# circuito_domotica_damiano.net
KiCad netlist of a schematic drawn in EAGLE
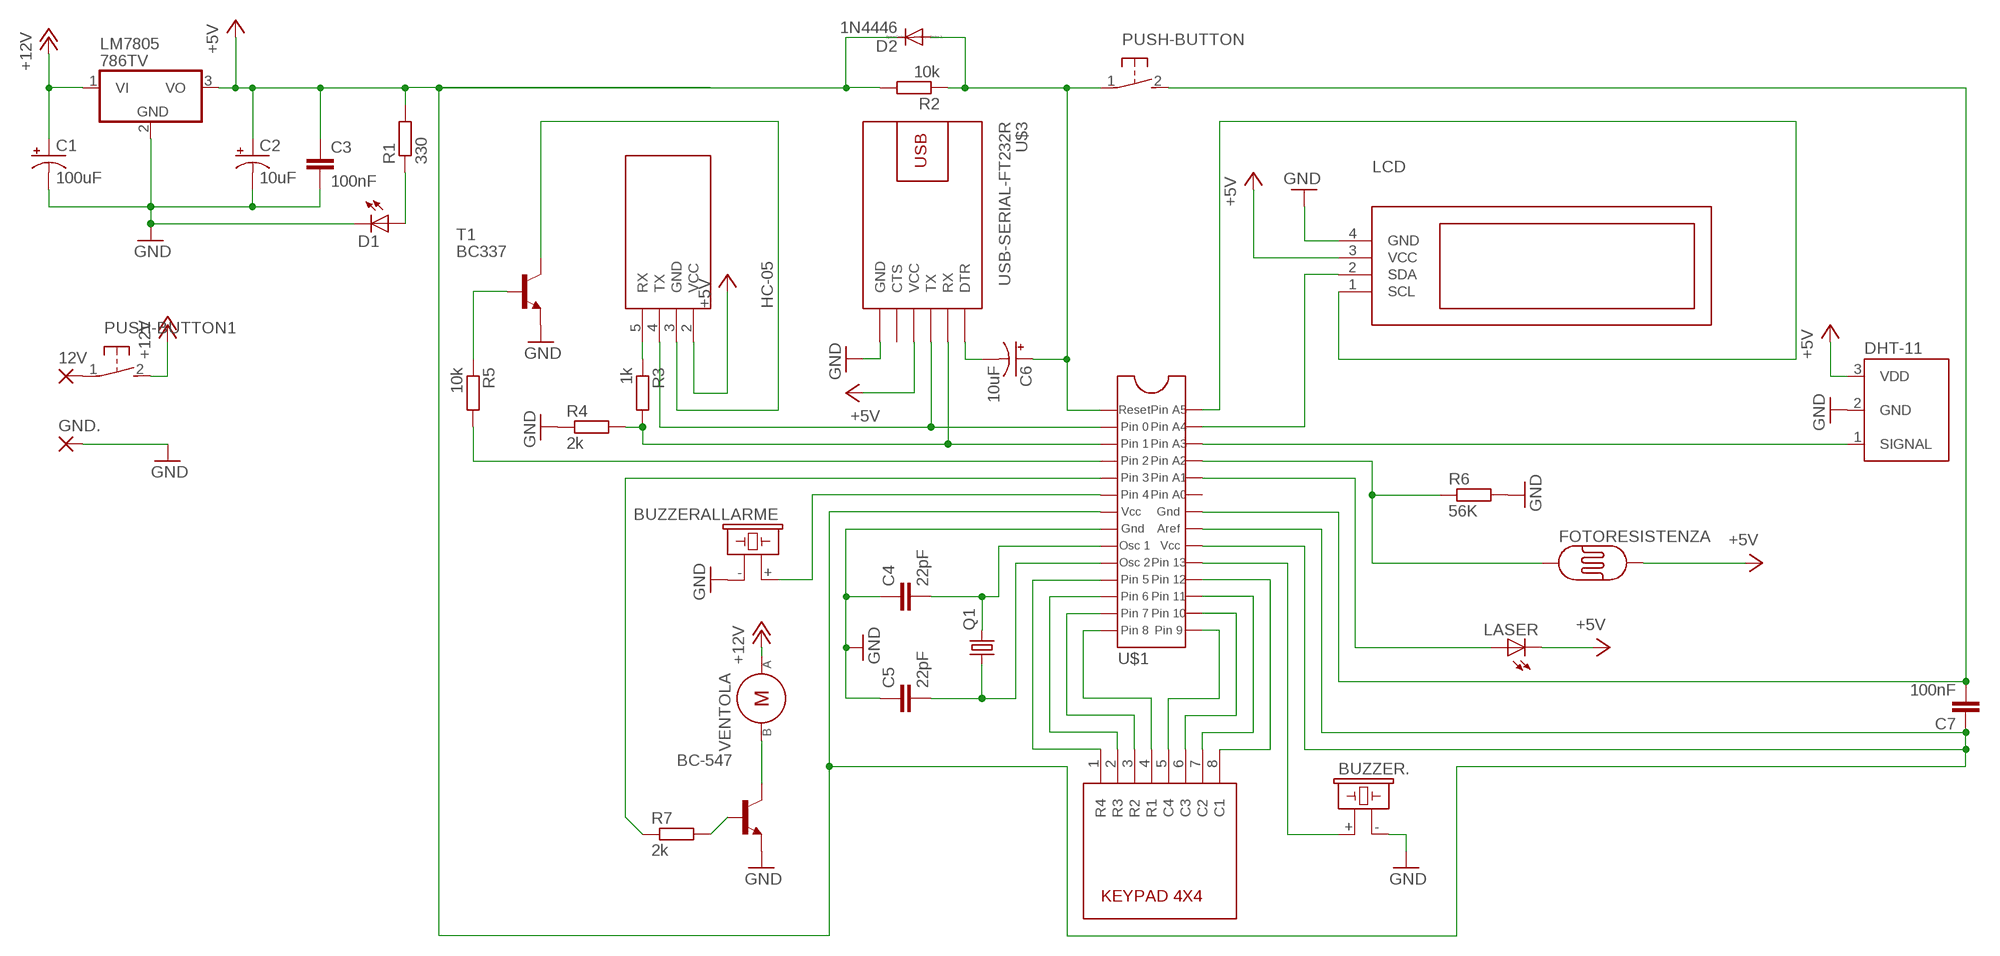
[diagram p0: schematic, sheet 1]

(export (version "E")
  (design (tool "Eeschema 10.0.6"))
  (components
    (comp (ref "12V")
      (value "WIREPAD1,6/0,8")
      (footprint "eagle-import:1,6_0,8")
      (libsource (lib "eagle-import") (part "WIREPAD1,6/0,8"))
    )
    (comp (ref "BC-547")
      (value "BC547-NPN-TO92-CBE")
      (footprint "eagle-import:TO92-CBE")
      (libsource (lib "eagle-import") (part "-NPN-TO92-CBEBC547"))
    )
    (comp (ref "BUZZER.")
      (value "BPT-24X")
      (footprint "eagle-import:BPT-24X")
      (libsource (lib "eagle-import") (part "BPT-24X"))
    )
    (comp (ref "BUZZERALLARME")
      (value "BPT-24X")
      (footprint "eagle-import:BPT-24X")
      (libsource (lib "eagle-import") (part "BPT-24X"))
    )
    (comp (ref "C1")
      (value "100uF")
      (footprint "eagle-import:E2,5-6E")
      (libsource (lib "eagle-import") (part "CPOL-USE2,5-6E"))
    )
    (comp (ref "C2")
      (value "10uF")
      (footprint "eagle-import:E2,5-6E")
      (libsource (lib "eagle-import") (part "CPOL-USE2,5-6E"))
    )
    (comp (ref "C3")
      (value "100nF")
      (footprint "eagle-import:C025-030X050")
      (libsource (lib "eagle-import") (part "C-EU025-030X050"))
    )
    (comp (ref "C4")
      (value "22pF")
      (footprint "eagle-import:C025-030X050")
      (libsource (lib "eagle-import") (part "C-EU025-030X050"))
    )
    (comp (ref "C5")
      (value "22pF")
      (footprint "eagle-import:C025-030X050")
      (libsource (lib "eagle-import") (part "C-EU025-030X050"))
    )
    (comp (ref "C6")
      (value "10uF")
      (footprint "eagle-import:E2,5-6E")
      (libsource (lib "eagle-import") (part "CPOL-USE2,5-6E"))
    )
    (comp (ref "C7")
      (value "100nF")
      (footprint "eagle-import:C025-030X050")
      (libsource (lib "eagle-import") (part "C-EU025-030X050"))
    )
    (comp (ref "D1")
      (value "SFH482")
      (footprint "eagle-import:SFH482")
      (libsource (lib "eagle-import") (part "SFH482"))
    )
    (comp (ref "D2")
      (value "1N4446")
      (footprint "eagle-import:DO35-10")
      (libsource (lib "eagle-import") (part "1N4446"))
    )
    (comp (ref "DHT-11")
      (value "DS18B20")
      (footprint "eagle-import:TO-92-AMMO")
      (libsource (lib "eagle-import") (part "DS18B20"))
    )
    (comp (ref "FOTORESISTENZA")
      (value "PHOTOCELLPTH")
      (footprint "eagle-import:PHOTOCELL")
      (libsource (lib "eagle-import") (part "PHOTOCELLPTH"))
    )
    (comp (ref "GND.")
      (value "WIREPAD1,6/0,8")
      (footprint "eagle-import:1,6_0,8")
      (libsource (lib "eagle-import") (part "WIREPAD1,6/0,8"))
    )
    (comp (ref "HC-05")
      (value "WIRELESS-BLUETOOTH-HC-05")
      (footprint "eagle-import:WIRELESS-BLUETOOTH-HC-05")
      (libsource (lib "eagle-import") (part "WIRELESS-BLUETOOTH-HC-05"))
    )
    (comp (ref "LASER")
      (value "SFH482")
      (footprint "eagle-import:SFH482")
      (libsource (lib "eagle-import") (part "SFH482"))
    )
    (comp (ref "LCD")
      (value "DISPLAY-OLED-128X32")
      (footprint "eagle-import:DISPLAY-OLED-128X32")
      (libsource (lib "eagle-import") (part "DISPLAY-OLED-128X32"))
    )
    (comp (ref "LM7805")
      (value "786TV")
      (footprint "eagle-import:TO220V")
      (libsource (lib "eagle-import") (part "78TV6"))
    )
    (comp (ref "PUSH-BUTTON")
      (value "DTS-3")
      (footprint "eagle-import:DTS-3")
      (libsource (lib "eagle-import") (part "DTS-3"))
    )
    (comp (ref "PUSH-BUTTON1")
      (value "DTS-3")
      (footprint "eagle-import:DTS-3")
      (libsource (lib "eagle-import") (part "DTS-3"))
    )
    (comp (ref "Q1")
      (value "CRYSTALHC49S")
      (footprint "eagle-import:HC49_S")
      (libsource (lib "eagle-import") (part "CRYSTALHC49S"))
    )
    (comp (ref "R1")
      (value "330")
      (footprint "eagle-import:0207_10")
      (libsource (lib "eagle-import") (part "R-EU_0207/10"))
    )
    (comp (ref "R2")
      (value "10k")
      (footprint "eagle-import:0207_10")
      (libsource (lib "eagle-import") (part "R-EU_0207/10"))
    )
    (comp (ref "R3")
      (value "1k")
      (footprint "eagle-import:0207_10")
      (libsource (lib "eagle-import") (part "R-EU_0207/10"))
    )
    (comp (ref "R4")
      (value "2k")
      (footprint "eagle-import:0207_10")
      (libsource (lib "eagle-import") (part "R-EU_0207/10"))
    )
    (comp (ref "R5")
      (value "10k")
      (footprint "eagle-import:0207_10")
      (libsource (lib "eagle-import") (part "R-EU_0207/10"))
    )
    (comp (ref "R6")
      (value "56K")
      (footprint "eagle-import:0207_10")
      (libsource (lib "eagle-import") (part "R-EU_0207/10"))
    )
    (comp (ref "R7")
      (value "2k")
      (footprint "eagle-import:0207_10")
      (libsource (lib "eagle-import") (part "R-EU_0207/10"))
    )
    (comp (ref "T1")
      (value "BC337")
      (footprint "eagle-import:TO92")
      (libsource (lib "eagle-import") (part "BC337"))
    )
    (comp (ref "U$1")
      (value "DEVU")
      (footprint "eagle-import:PACU")
      (libsource (lib "eagle-import") (part "DEVU"))
    )
    (comp (ref "U$2")
      (value "KEYPAD4X4")
      (footprint "eagle-import:KEYPAD4X4")
      (libsource (lib "eagle-import") (part "KEYPAD4X4"))
    )
    (comp (ref "U$3")
      (value "USB-SERIAL-FT232R")
      (footprint "eagle-import:USB-SERIAL-FT232R")
      (libsource (lib "eagle-import") (part "USB-SERIAL-FT232R"))
    )
    (comp (ref "VENTOLA")
      (value "DEVU4")
      (footprint "eagle-import:PACU4")
      (libsource (lib "eagle-import") (part "DEVU4"))
    )
  )
  (nets
    (net (code "1") (name "+5V") (class "Default")
      (node (ref "C2") (pin "+") (pinfunction "+_+") (pintype "passive"))
      (node (ref "C3") (pin "1") (pinfunction "1_1") (pintype "passive"))
      (node (ref "C7") (pin "1") (pinfunction "1_1") (pintype "passive"))
      (node (ref "D2") (pin "C") (pinfunction "C_C") (pintype "passive"))
      (node (ref "DHT-11") (pin "3") (pinfunction "VDD_3") (pintype "power_in"))
      (node (ref "FOTORESISTENZA") (pin "2") (pinfunction "P$2_2") (pintype "bidirectional"))
      (node (ref "HC-05") (pin "2") (pinfunction "VCC_2") (pintype "bidirectional"))
      (node (ref "LASER") (pin "K") (pinfunction "C_K") (pintype "passive"))
      (node (ref "LCD") (pin "3") (pinfunction "VCC_3") (pintype "bidirectional"))
      (node (ref "LM7805") (pin "3") (pinfunction "VO_3") (pintype "passive"))
      (node (ref "R1") (pin "2") (pinfunction "2_2") (pintype "passive"))
      (node (ref "R2") (pin "2") (pinfunction "2_2") (pintype "passive"))
      (node (ref "U$1") (pin "20") (pinfunction "VCC1_20") (pintype "bidirectional"))
      (node (ref "U$1") (pin "21") (pinfunction "AREF_21") (pintype "bidirectional"))
      (node (ref "U$1") (pin "7") (pinfunction "VCC_7") (pintype "bidirectional"))
      (node (ref "U$3") (pin "4") (pinfunction "VCC_4") (pintype "power_in"))
    )
    (net (code "2") (name "+12V") (class "Default")
      (node (ref "C1") (pin "+") (pinfunction "+_+") (pintype "passive"))
      (node (ref "LM7805") (pin "1") (pinfunction "VI_1") (pintype "input"))
      (node (ref "PUSH-BUTTON1") (pin "2") (pinfunction "2_2") (pintype "passive"))
      (node (ref "VENTOLA") (pin "P$1") (pinfunction "P$1_P$1") (pintype "bidirectional"))
    )
    (net (code "3") (name "GND") (class "Default")
      (node (ref "BC-547") (pin "E") (pinfunction "E_E") (pintype "passive"))
      (node (ref "BUZZER.") (pin "-") (pinfunction "2_-") (pintype "passive"))
      (node (ref "BUZZERALLARME") (pin "-") (pinfunction "2_-") (pintype "passive"))
      (node (ref "C1") (pin "-") (pinfunction "-_-") (pintype "passive"))
      (node (ref "C2") (pin "-") (pinfunction "-_-") (pintype "passive"))
      (node (ref "C3") (pin "2") (pinfunction "2_2") (pintype "passive"))
      (node (ref "C4") (pin "1") (pinfunction "1_1") (pintype "passive"))
      (node (ref "C5") (pin "1") (pinfunction "1_1") (pintype "passive"))
      (node (ref "D1") (pin "K") (pinfunction "C_K") (pintype "passive"))
      (node (ref "DHT-11") (pin "2") (pinfunction "GND_2") (pintype "bidirectional"))
      (node (ref "GND.") (pin "1") (pinfunction "P_1") (pintype "passive"))
      (node (ref "LCD") (pin "4") (pinfunction "GND_4") (pintype "bidirectional"))
      (node (ref "LM7805") (pin "2") (pinfunction "GND_2") (pintype "passive"))
      (node (ref "R4") (pin "1") (pinfunction "1_1") (pintype "passive"))
      (node (ref "R6") (pin "2") (pinfunction "2_2") (pintype "passive"))
      (node (ref "T1") (pin "1") (pinfunction "E_1") (pintype "passive"))
      (node (ref "U$1") (pin "8") (pinfunction "GND_8") (pintype "bidirectional"))
      (node (ref "U$3") (pin "6") (pinfunction "GND_6") (pintype "bidirectional"))
    )
    (net (code "4") (name "Net-(12V-P)") (class "Default")
      (node (ref "12V") (pin "1") (pinfunction "P_1") (pintype "passive"))
      (node (ref "PUSH-BUTTON1") (pin "1") (pinfunction "1_1") (pintype "passive"))
    )
    (net (code "5") (name "Net-(BC-547-PadB)") (class "Default")
      (node (ref "BC-547") (pin "B") (pinfunction "B_B") (pintype "passive"))
      (node (ref "R7") (pin "2") (pinfunction "2_2") (pintype "passive"))
    )
    (net (code "6") (name "Net-(BC-547-PadC)") (class "Default")
      (node (ref "BC-547") (pin "C") (pinfunction "C_C") (pintype "passive"))
      (node (ref "VENTOLA") (pin "P$2") (pinfunction "P$2_P$2") (pintype "bidirectional"))
    )
    (net (code "7") (name "Net-(BUZZER.-1)") (class "Default")
      (node (ref "BUZZER.") (pin "+") (pinfunction "1_+") (pintype "passive"))
      (node (ref "U$1") (pin "19") (pinfunction "PIN13_19") (pintype "bidirectional"))
    )
    (net (code "8") (name "Net-(BUZZERALLARME-1)") (class "Default")
      (node (ref "BUZZERALLARME") (pin "+") (pinfunction "1_+") (pintype "passive"))
      (node (ref "U$1") (pin "6") (pinfunction "PIN4_6") (pintype "bidirectional"))
    )
    (net (code "9") (name "Net-(D1-PadA)") (class "Default")
      (node (ref "D1") (pin "A") (pinfunction "A_A") (pintype "passive"))
      (node (ref "R1") (pin "1") (pinfunction "1_1") (pintype "passive"))
    )
    (net (code "10") (name "Net-(DHT-11-SIGNAL)") (class "Default")
      (node (ref "DHT-11") (pin "1") (pinfunction "SIGNAL_1") (pintype "power_in"))
      (node (ref "U$1") (pin "26") (pinfunction "PINA3_26") (pintype "bidirectional"))
    )
    (net (code "11") (name "Net-(FOTORESISTENZA-P$1)") (class "Default")
      (node (ref "FOTORESISTENZA") (pin "1") (pinfunction "P$1_1") (pintype "bidirectional"))
      (node (ref "R6") (pin "1") (pinfunction "1_1") (pintype "passive"))
      (node (ref "U$1") (pin "25") (pinfunction "PINA2_25") (pintype "bidirectional"))
    )
    (net (code "12") (name "Net-(HC-05-GND)") (class "Default")
      (node (ref "HC-05") (pin "3") (pinfunction "GND_3") (pintype "bidirectional"))
      (node (ref "T1") (pin "3") (pinfunction "C_3") (pintype "passive"))
    )
    (net (code "13") (name "Net-(HC-05-RX)") (class "Default")
      (node (ref "HC-05") (pin "5") (pinfunction "RX_5") (pintype "power_in"))
      (node (ref "R3") (pin "1") (pinfunction "1_1") (pintype "passive"))
    )
    (net (code "14") (name "Net-(HC-05-TX)") (class "Default")
      (node (ref "HC-05") (pin "4") (pinfunction "TX_4") (pintype "power_in"))
      (node (ref "U$1") (pin "2") (pinfunction "PIN0_2") (pintype "bidirectional"))
      (node (ref "U$3") (pin "3") (pinfunction "TX_3") (pintype "bidirectional"))
    )
    (net (code "15") (name "Net-(LCD-SCL)") (class "Default")
      (node (ref "LCD") (pin "1") (pinfunction "SCL_1") (pintype "power_in"))
      (node (ref "U$1") (pin "28") (pinfunction "PINA5_28") (pintype "bidirectional"))
    )
    (net (code "16") (name "Net-(LCD-SDA)") (class "Default")
      (node (ref "LCD") (pin "2") (pinfunction "SDA_2") (pintype "power_in"))
      (node (ref "U$1") (pin "27") (pinfunction "PINA4_27") (pintype "bidirectional"))
    )
    (net (code "17") (name "Net-(T1-B)") (class "Default")
      (node (ref "R5") (pin "1") (pinfunction "1_1") (pintype "passive"))
      (node (ref "T1") (pin "2") (pinfunction "B_2") (pintype "passive"))
    )
    (net (code "18") (name "Net-(U$1-GND1)") (class "Default")
      (node (ref "C7") (pin "2") (pinfunction "2_2") (pintype "passive"))
      (node (ref "PUSH-BUTTON") (pin "2") (pinfunction "2_2") (pintype "passive"))
      (node (ref "U$1") (pin "22") (pinfunction "GND1_22") (pintype "bidirectional"))
    )
    (net (code "19") (name "Net-(U$1-PIN1)") (class "Default")
      (node (ref "R3") (pin "2") (pinfunction "2_2") (pintype "passive"))
      (node (ref "R4") (pin "2") (pinfunction "2_2") (pintype "passive"))
      (node (ref "U$1") (pin "3") (pinfunction "PIN1_3") (pintype "bidirectional"))
      (node (ref "U$3") (pin "2") (pinfunction "RX_2") (pintype "bidirectional"))
    )
    (net (code "20") (name "Net-(U$1-PIN2)") (class "Default")
      (node (ref "R5") (pin "2") (pinfunction "2_2") (pintype "passive"))
      (node (ref "U$1") (pin "4") (pinfunction "PIN2_4") (pintype "bidirectional"))
    )
    (net (code "21") (name "Net-(U$1-PIN3)") (class "Default")
      (node (ref "R7") (pin "1") (pinfunction "1_1") (pintype "passive"))
      (node (ref "U$1") (pin "5") (pinfunction "PIN3_5") (pintype "bidirectional"))
    )
    (net (code "22") (name "Net-(U$1-PIN5)") (class "Default")
      (node (ref "U$1") (pin "11") (pinfunction "PIN5_11") (pintype "bidirectional"))
      (node (ref "U$2") (pin "1") (pinfunction "R4_1") (pintype "bidirectional"))
    )
    (net (code "23") (name "Net-(U$1-PIN6)") (class "Default")
      (node (ref "U$1") (pin "12") (pinfunction "PIN6_12") (pintype "bidirectional"))
      (node (ref "U$2") (pin "2") (pinfunction "R3_2") (pintype "bidirectional"))
    )
    (net (code "24") (name "Net-(U$1-PIN7)") (class "Default")
      (node (ref "U$1") (pin "13") (pinfunction "PIN7_13") (pintype "bidirectional"))
      (node (ref "U$2") (pin "3") (pinfunction "R2_3") (pintype "bidirectional"))
    )
    (net (code "25") (name "Net-(U$1-PIN8)") (class "Default")
      (node (ref "U$1") (pin "14") (pinfunction "PIN8_14") (pintype "bidirectional"))
      (node (ref "U$2") (pin "4") (pinfunction "R1_4") (pintype "bidirectional"))
    )
    (net (code "26") (name "Net-(U$1-PIN9)") (class "Default")
      (node (ref "U$1") (pin "15") (pinfunction "PIN9_15") (pintype "bidirectional"))
      (node (ref "U$2") (pin "5") (pinfunction "C4_5") (pintype "bidirectional"))
    )
    (net (code "27") (name "Net-(U$1-PIN10)") (class "Default")
      (node (ref "U$1") (pin "16") (pinfunction "PIN10_16") (pintype "bidirectional"))
      (node (ref "U$2") (pin "6") (pinfunction "C3_6") (pintype "bidirectional"))
    )
    (net (code "28") (name "Net-(U$1-PIN11)") (class "Default")
      (node (ref "U$1") (pin "17") (pinfunction "PIN11_17") (pintype "bidirectional"))
      (node (ref "U$2") (pin "7") (pinfunction "C2_7") (pintype "bidirectional"))
    )
    (net (code "29") (name "Net-(U$1-PIN12)") (class "Default")
      (node (ref "U$1") (pin "18") (pinfunction "PIN12_18") (pintype "bidirectional"))
      (node (ref "U$2") (pin "8") (pinfunction "C1_8") (pintype "bidirectional"))
    )
    (net (code "30") (name "Net-(U$1-PINA1)") (class "Default")
      (node (ref "LASER") (pin "A") (pinfunction "A_A") (pintype "passive"))
      (node (ref "U$1") (pin "24") (pinfunction "PINA1_24") (pintype "bidirectional"))
    )
    (net (code "31") (name "Net-(U$1-RESET)") (class "Default")
      (node (ref "C6") (pin "+") (pinfunction "+_+") (pintype "passive"))
      (node (ref "D2") (pin "A") (pinfunction "A_A") (pintype "passive"))
      (node (ref "PUSH-BUTTON") (pin "1") (pinfunction "1_1") (pintype "passive"))
      (node (ref "R2") (pin "1") (pinfunction "1_1") (pintype "passive"))
      (node (ref "U$1") (pin "1") (pinfunction "RESET_1") (pintype "bidirectional"))
    )
    (net (code "32") (name "Net-(U$1-X1)") (class "Default")
      (node (ref "C4") (pin "2") (pinfunction "2_2") (pintype "passive"))
      (node (ref "Q1") (pin "2") (pinfunction "2_2") (pintype "passive"))
      (node (ref "U$1") (pin "9") (pinfunction "X1_9") (pintype "bidirectional"))
    )
    (net (code "33") (name "Net-(U$1-X2)") (class "Default")
      (node (ref "C5") (pin "2") (pinfunction "2_2") (pintype "passive"))
      (node (ref "Q1") (pin "1") (pinfunction "1_1") (pintype "passive"))
      (node (ref "U$1") (pin "10") (pinfunction "X2_10") (pintype "bidirectional"))
    )
    (net (code "34") (name "Net-(U$3-DTR)") (class "Default")
      (node (ref "C6") (pin "-") (pinfunction "-_-") (pintype "passive"))
      (node (ref "U$3") (pin "1") (pinfunction "DTR_1") (pintype "bidirectional"))
    )
    (net (code "35") (name "unconnected-(U$1-PINA0-Pad23)") (class "Default")
      (node (ref "U$1") (pin "23") (pinfunction "PINA0_23") (pintype "bidirectional"))
    )
    (net (code "36") (name "unconnected-(U$3-CTS-Pad5)") (class "Default")
      (node (ref "U$3") (pin "5") (pinfunction "CTS_5") (pintype "bidirectional"))
    )
  )
)
